# 09_-_CPU_-_SD_AUDIO_I2C_CAN.net
KiCad netlist of a schematic drawn in Altium Designer
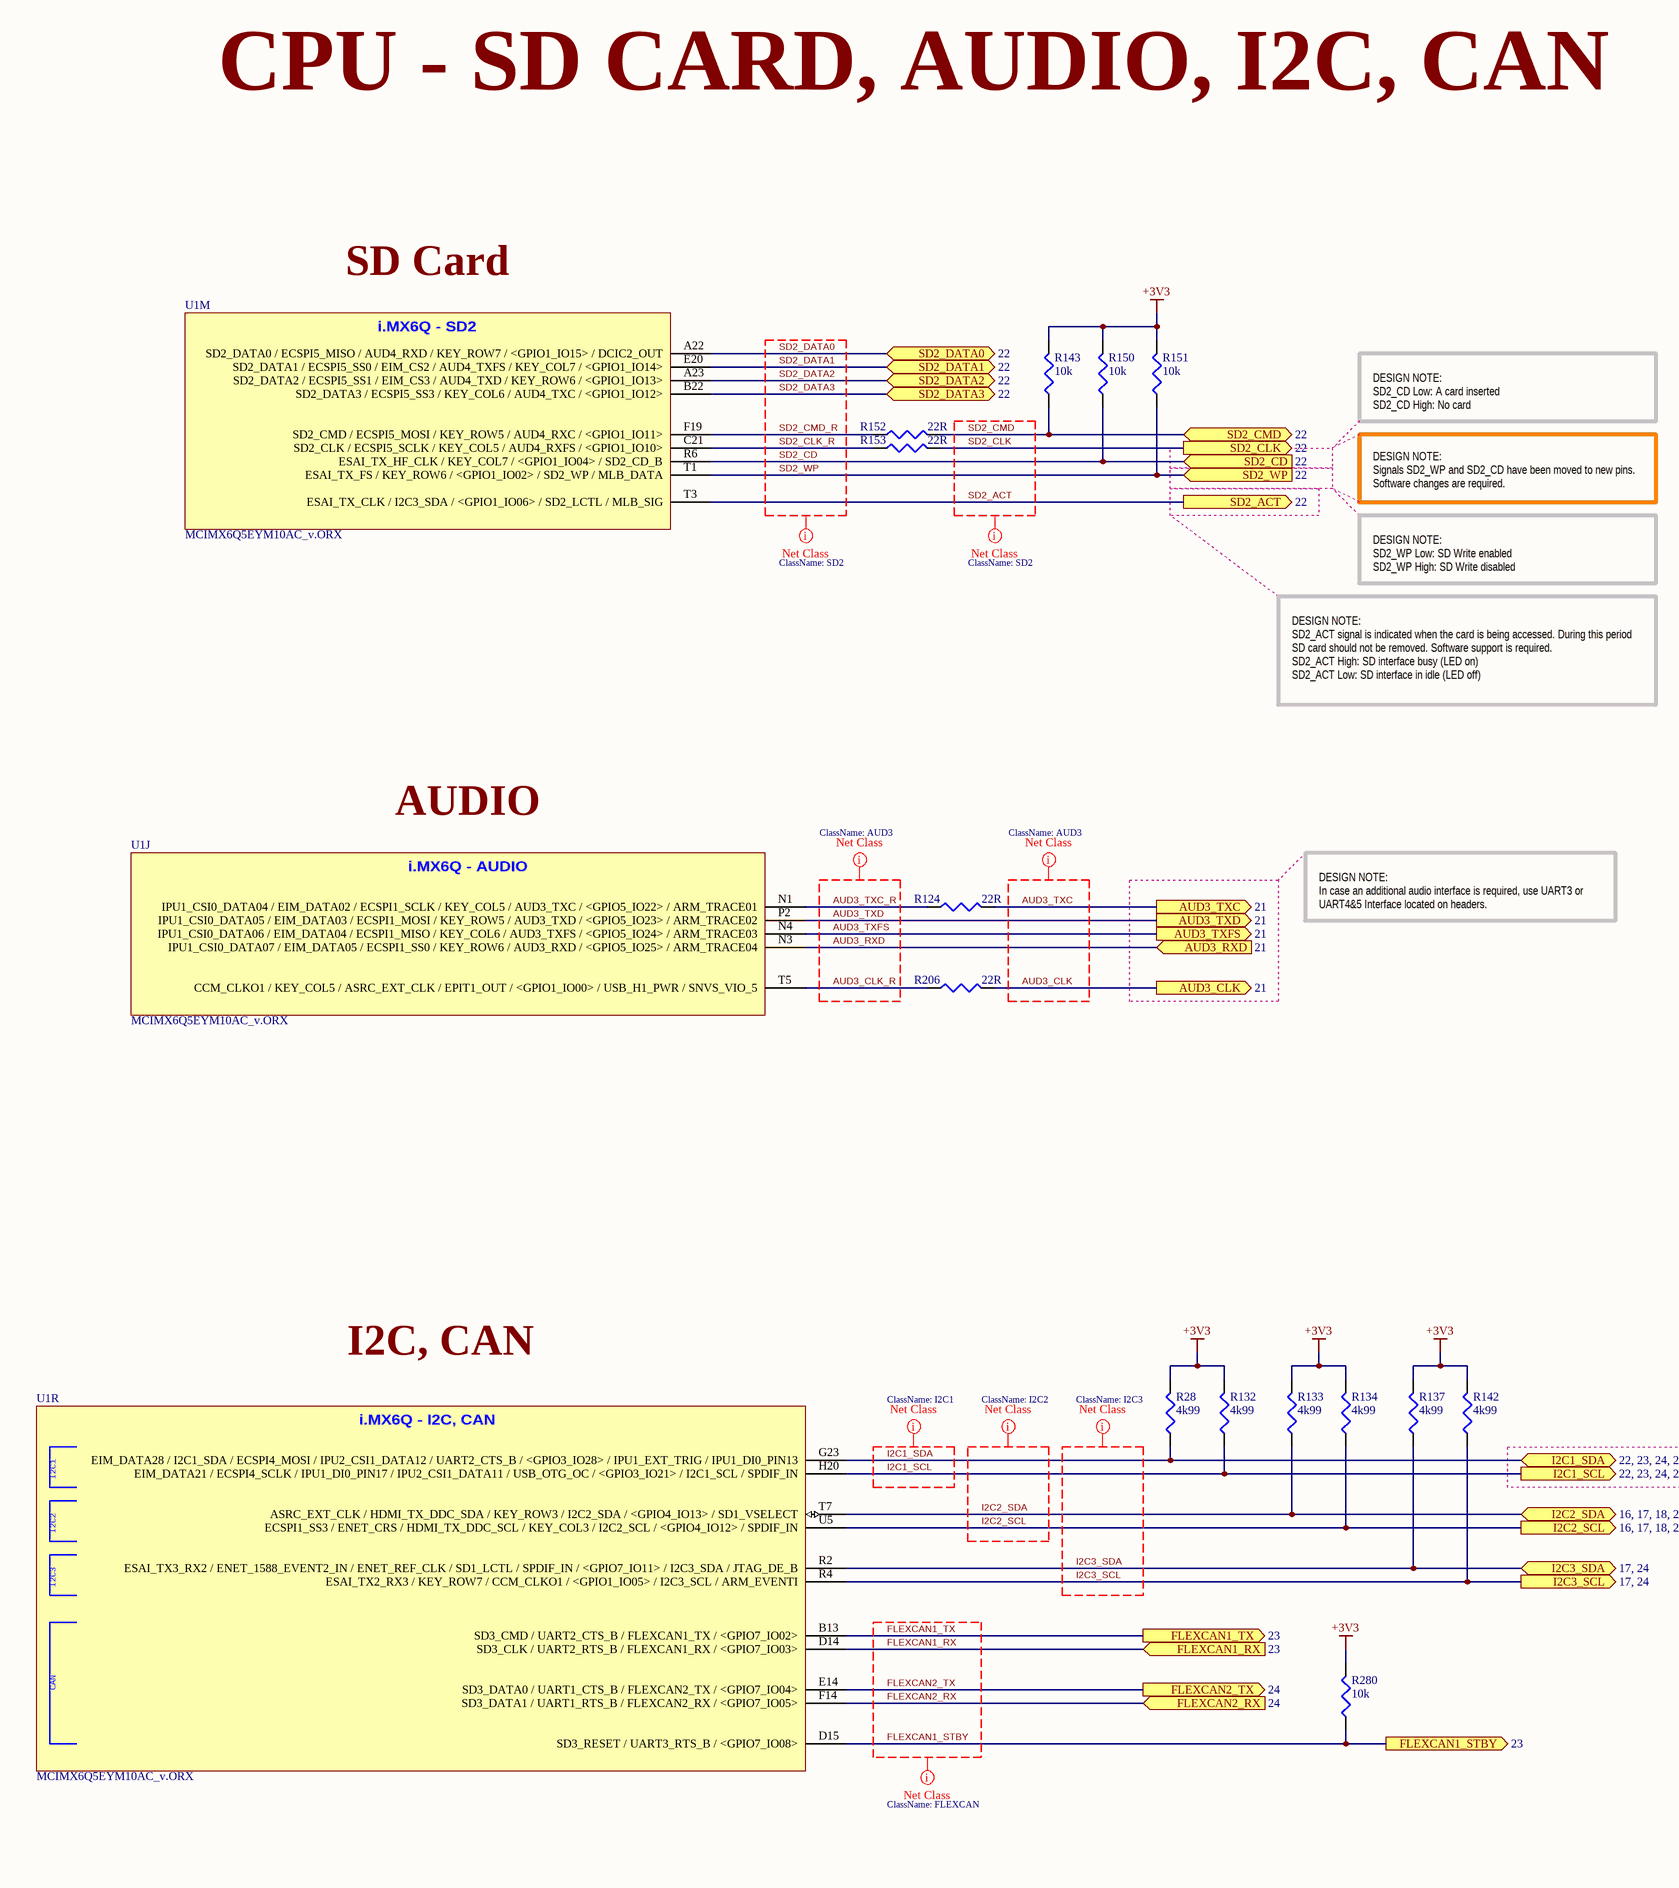
[diagram p0: [09] - CPU - SD, AUDIO, I2C, CAN.SchDoc, left]
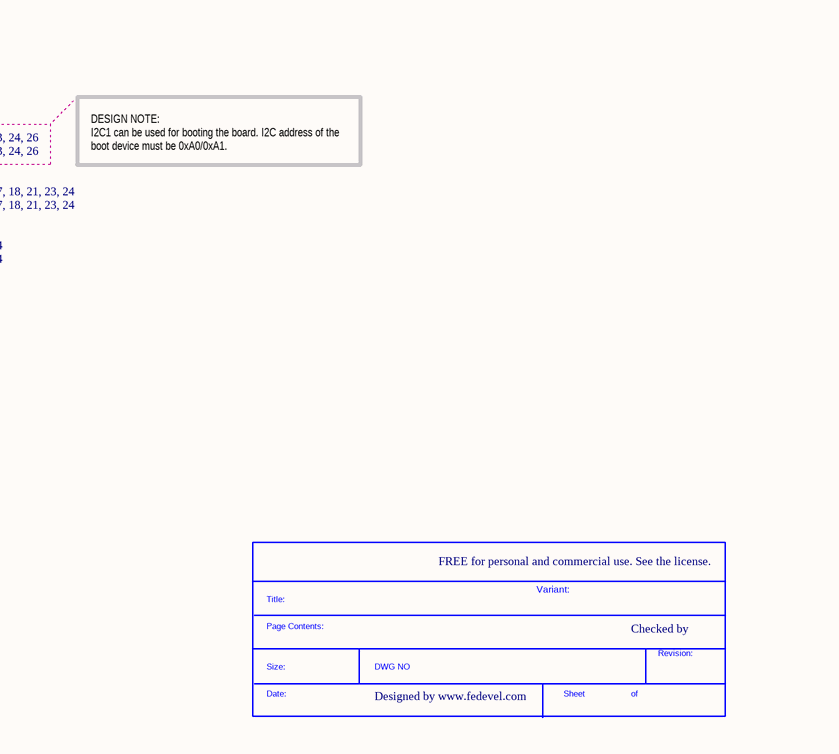
[diagram p1: [09] - CPU - SD, AUDIO, I2C, CAN.SchDoc, right]

(export (version "E")
  (design (tool "Eeschema 10.0.6"))
  (components
    (comp (ref "R28")
      (value "4k99")
      (footprint "R0402")
      (description "RES TF 4.99K OHM 1% 1/16W 0402")
      (fields
        (field (name "MANUFACTURER") "Stackpole Electronics Inc")
        (field (name "MANUFACTURER PART NUMBER") "RMCF0402FT4K99")
      )
      (libsource (lib "Integrated_Library_FEDEVEL_APR_2015") (part "RMCF0402FT4K99"))
    )
    (comp (ref "R124")
      (value "22R")
      (footprint "R0402")
      (description "RES 22.0 OHM 1/16W 1% 0402 SMD")
      (fields
        (field (name "MANUFACTURER") "Yageo")
        (field (name "MANUFACTURER PART NUMBER") "RC0402FR-0722RL")
      )
      (libsource (lib "Integrated_Library_FEDEVEL_APR_2015") (part "RC0402FR-0722RL"))
    )
    (comp (ref "R132")
      (value "4k99")
      (footprint "R0402")
      (description "RES TF 4.99K OHM 1% 1/16W 0402")
      (fields
        (field (name "MANUFACTURER") "Stackpole Electronics Inc")
        (field (name "MANUFACTURER PART NUMBER") "RMCF0402FT4K99")
      )
      (libsource (lib "Integrated_Library_FEDEVEL_APR_2015") (part "RMCF0402FT4K99"))
    )
    (comp (ref "R133")
      (value "4k99")
      (footprint "R0402")
      (description "RES TF 4.99K OHM 1% 1/16W 0402")
      (fields
        (field (name "MANUFACTURER") "Stackpole Electronics Inc")
        (field (name "MANUFACTURER PART NUMBER") "RMCF0402FT4K99")
      )
      (libsource (lib "Integrated_Library_FEDEVEL_APR_2015") (part "RMCF0402FT4K99"))
    )
    (comp (ref "R134")
      (value "4k99")
      (footprint "R0402")
      (description "RES TF 4.99K OHM 1% 1/16W 0402")
      (fields
        (field (name "MANUFACTURER") "Stackpole Electronics Inc")
        (field (name "MANUFACTURER PART NUMBER") "RMCF0402FT4K99")
      )
      (libsource (lib "Integrated_Library_FEDEVEL_APR_2015") (part "RMCF0402FT4K99"))
    )
    (comp (ref "R137")
      (value "4k99")
      (footprint "R0402")
      (description "RES TF 4.99K OHM 1% 1/16W 0402")
      (fields
        (field (name "MANUFACTURER") "Stackpole Electronics Inc")
        (field (name "MANUFACTURER PART NUMBER") "RMCF0402FT4K99")
      )
      (libsource (lib "Integrated_Library_FEDEVEL_APR_2015") (part "RMCF0402FT4K99"))
    )
    (comp (ref "R142")
      (value "4k99")
      (footprint "R0402")
      (description "RES TF 4.99K OHM 1% 1/16W 0402")
      (fields
        (field (name "MANUFACTURER") "Stackpole Electronics Inc")
        (field (name "MANUFACTURER PART NUMBER") "RMCF0402FT4K99")
      )
      (libsource (lib "Integrated_Library_FEDEVEL_APR_2015") (part "RMCF0402FT4K99"))
    )
    (comp (ref "R143")
      (value "10k")
      (footprint "R0402")
      (description "RES 10.0K OHM 1/16W 1% 0402 SMD")
      (fields
        (field (name "MANUFACTURER") "Yageo")
        (field (name "MANUFACTURER PART NUMBER") "RC0402FR-0710KL")
      )
      (libsource (lib "Integrated_Library_FEDEVEL_APR_2015") (part "RC0402FR-0710KL"))
    )
    (comp (ref "R150")
      (value "10k")
      (footprint "R0402")
      (description "RES 10.0K OHM 1/16W 1% 0402 SMD")
      (fields
        (field (name "MANUFACTURER") "Yageo")
        (field (name "MANUFACTURER PART NUMBER") "RC0402FR-0710KL")
      )
      (libsource (lib "Integrated_Library_FEDEVEL_APR_2015") (part "RC0402FR-0710KL"))
    )
    (comp (ref "R151")
      (value "10k")
      (footprint "R0402")
      (description "RES 10.0K OHM 1/16W 1% 0402 SMD")
      (fields
        (field (name "MANUFACTURER") "Yageo")
        (field (name "MANUFACTURER PART NUMBER") "RC0402FR-0710KL")
      )
      (libsource (lib "Integrated_Library_FEDEVEL_APR_2015") (part "RC0402FR-0710KL"))
    )
    (comp (ref "R152")
      (value "22R")
      (footprint "R0402")
      (description "RES 22.0 OHM 1/16W 1% 0402 SMD")
      (fields
        (field (name "MANUFACTURER") "Yageo")
        (field (name "MANUFACTURER PART NUMBER") "RC0402FR-0722RL")
      )
      (libsource (lib "Integrated_Library_FEDEVEL_APR_2015") (part "RC0402FR-0722RL"))
    )
    (comp (ref "R153")
      (value "22R")
      (footprint "R0402")
      (description "RES 22.0 OHM 1/16W 1% 0402 SMD")
      (fields
        (field (name "MANUFACTURER") "Yageo")
        (field (name "MANUFACTURER PART NUMBER") "RC0402FR-0722RL")
      )
      (libsource (lib "Integrated_Library_FEDEVEL_APR_2015") (part "RC0402FR-0722RL"))
    )
    (comp (ref "R206")
      (value "22R")
      (footprint "R0402")
      (description "RES 22.0 OHM 1/16W 1% 0402 SMD")
      (fields
        (field (name "MANUFACTURER") "Yageo")
        (field (name "MANUFACTURER PART NUMBER") "RC0402FR-0722RL")
      )
      (libsource (lib "Integrated_Library_FEDEVEL_APR_2015") (part "RC0402FR-0722RL"))
    )
    (comp (ref "R280")
      (value "10k")
      (footprint "R0402")
      (description "RES 10.0K OHM 1/16W 1% 0402 SMD")
      (fields
        (field (name "MANUFACTURER") "Yageo")
        (field (name "MANUFACTURER PART NUMBER") "RC0402FR-0710KL")
      )
      (libsource (lib "Integrated_Library_FEDEVEL_APR_2015") (part "RC0402FR-0710KL"))
    )
    (comp (ref "U1")
      (value "MCIMX6Q5EYM10AC_v.ORX")
      (footprint "PBGA624")
      (description "IC MCU 32BIT ARM QUAD 624FCBGA")
      (fields
        (field (name "MANUFACTURER") "Freescale Semiconductor")
        (field (name "MANUFACTURER PART NUMBER") "MCIMX6Q5EYM10AC")
        (field (name ".CREATOR") "MM")
        (field (name ".CHECKED PCB") "MM, checked by RF")
      )
      (libsource (lib "Integrated_Library_FEDEVEL_APR_2015") (part "MCIMX6Q5EYM10AC_v.ORX"))
    )
  )
  (nets
    (net (code "1") (name "+3V3") (class "Default")
      (node (ref "R132") (pin "2") (pinfunction "2_2") (pintype "passive"))
      (node (ref "R133") (pin "2") (pinfunction "2_2") (pintype "passive"))
      (node (ref "R134") (pin "2") (pinfunction "2_2") (pintype "passive"))
      (node (ref "R137") (pin "2") (pinfunction "2_2") (pintype "passive"))
      (node (ref "R142") (pin "2") (pinfunction "2_2") (pintype "passive"))
      (node (ref "R143") (pin "2") (pinfunction "2_2") (pintype "passive"))
      (node (ref "R150") (pin "2") (pinfunction "2_2") (pintype "passive"))
      (node (ref "R151") (pin "2") (pinfunction "2_2") (pintype "passive"))
      (node (ref "R28") (pin "2") (pinfunction "2_2") (pintype "passive"))
      (node (ref "R280") (pin "2") (pinfunction "2_2") (pintype "passive"))
    )
    (net (code "2") (name "/AUD3_CLK") (class "Default")
      (node (ref "R206") (pin "2") (pinfunction "2_2") (pintype "passive"))
    )
    (net (code "3") (name "/AUD3_CLK_R") (class "Default")
      (node (ref "R206") (pin "1") (pinfunction "1_1") (pintype "passive"))
      (node (ref "U1") (pin "T5") (pinfunction "CCM_CLKO1_/_KEY_COL5_/_ASRC_EXT_CLK_/_EPIT1_OUT_/_<GPIO1_IO00>_/_USB_H1_PWR_/_SNVS_VIO_5_T5") (pintype "passive"))
    )
    (net (code "4") (name "/AUD3_RXD") (class "Default")
      (node (ref "U1") (pin "N3") (pinfunction "IPU1_CSI0_DATA07_/_EIM_DATA05_/_ECSPI1_SS0_/_KEY_ROW6_/_AUD3_RXD_/_<GPIO5_IO25>_/_ARM_TRACE04_N3") (pintype "passive"))
    )
    (net (code "5") (name "/AUD3_TXC") (class "Default")
      (node (ref "R124") (pin "2") (pinfunction "2_2") (pintype "passive"))
    )
    (net (code "6") (name "/AUD3_TXC_R") (class "Default")
      (node (ref "R124") (pin "1") (pinfunction "1_1") (pintype "passive"))
      (node (ref "U1") (pin "N1") (pinfunction "IPU1_CSI0_DATA04_/_EIM_DATA02_/_ECSPI1_SCLK_/_KEY_COL5_/_AUD3_TXC_/_<GPIO5_IO22>_/_ARM_TRACE01_N1") (pintype "passive"))
    )
    (net (code "7") (name "/AUD3_TXD") (class "Default")
      (node (ref "U1") (pin "P2") (pinfunction "IPU1_CSI0_DATA05_/_EIM_DATA03_/_ECSPI1_MOSI_/_KEY_ROW5_/_AUD3_TXD_/_<GPIO5_IO23>_/_ARM_TRACE02_P2") (pintype "passive"))
    )
    (net (code "8") (name "/AUD3_TXFS") (class "Default")
      (node (ref "U1") (pin "N4") (pinfunction "IPU1_CSI0_DATA06_/_EIM_DATA04_/_ECSPI1_MISO_/_KEY_COL6_/_AUD3_TXFS_/_<GPIO5_IO24>_/_ARM_TRACE03_N4") (pintype "passive"))
    )
    (net (code "9") (name "/FLEXCAN1_RX") (class "Default")
      (node (ref "U1") (pin "D14") (pinfunction "SD3_CLK_/_UART2_RTS_B_/_FLEXCAN1_RX_/_<GPIO7_IO03>_D14") (pintype "passive"))
    )
    (net (code "10") (name "/FLEXCAN1_STBY") (class "Default")
      (node (ref "R280") (pin "1") (pinfunction "1_1") (pintype "passive"))
      (node (ref "U1") (pin "D15") (pinfunction "SD3_RESET_/_UART3_RTS_B_/_<GPIO7_IO08>_D15") (pintype "passive"))
    )
    (net (code "11") (name "/FLEXCAN1_TX") (class "Default")
      (node (ref "U1") (pin "B13") (pinfunction "SD3_CMD_/_UART2_CTS_B_/_FLEXCAN1_TX_/_<GPIO7_IO02>_B13") (pintype "passive"))
    )
    (net (code "12") (name "/FLEXCAN2_RX") (class "Default")
      (node (ref "U1") (pin "F14") (pinfunction "SD3_DATA1_/_UART1_RTS_B_/_FLEXCAN2_RX_/_<GPIO7_IO05>_F14") (pintype "passive"))
    )
    (net (code "13") (name "/FLEXCAN2_TX") (class "Default")
      (node (ref "U1") (pin "E14") (pinfunction "SD3_DATA0_/_UART1_CTS_B_/_FLEXCAN2_TX_/_<GPIO7_IO04>_E14") (pintype "passive"))
    )
    (net (code "14") (name "/I2C1_SCL") (class "Default")
      (node (ref "R132") (pin "1") (pinfunction "1_1") (pintype "passive"))
      (node (ref "U1") (pin "H20") (pinfunction "EIM_DATA21_/_ECSPI4_SCLK_/_IPU1_DI0_PIN17_/_IPU2_CSI1_DATA11_/_USB_OTG_OC_/_<GPIO3_IO21>_/_I2C1_SCL_/_SPDIF_IN_H20") (pintype "passive"))
    )
    (net (code "15") (name "/I2C1_SDA") (class "Default")
      (node (ref "R28") (pin "1") (pinfunction "1_1") (pintype "passive"))
      (node (ref "U1") (pin "G23") (pinfunction "EIM_DATA28_/_I2C1_SDA_/_ECSPI4_MOSI_/_IPU2_CSI1_DATA12_/_UART2_CTS_B_/_<GPIO3_IO28>_/_IPU1_EXT_TRIG_/_IPU1_DI0_PIN13_G23") (pintype "passive"))
    )
    (net (code "16") (name "/I2C2_SCL") (class "Default")
      (node (ref "R134") (pin "1") (pinfunction "1_1") (pintype "passive"))
      (node (ref "U1") (pin "U5") (pinfunction "ECSPI1_SS3_/_ENET_CRS_/_HDMI_TX_DDC_SCL_/_KEY_COL3_/_I2C2_SCL_/_<GPIO4_IO12>_/_SPDIF_IN_U5") (pintype "passive"))
    )
    (net (code "17") (name "/I2C2_SDA") (class "Default")
      (node (ref "R133") (pin "1") (pinfunction "1_1") (pintype "passive"))
      (node (ref "U1") (pin "T7") (pinfunction "ASRC_EXT_CLK_/_HDMI_TX_DDC_SDA_/_KEY_ROW3_/_I2C2_SDA_/_<GPIO4_IO13>_/_SD1_VSELECT_T7") (pintype "bidirectional"))
    )
    (net (code "18") (name "/I2C3_SCL") (class "Default")
      (node (ref "R142") (pin "1") (pinfunction "1_1") (pintype "passive"))
      (node (ref "U1") (pin "R4") (pinfunction "ESAI_TX2_RX3_/_KEY_ROW7_/_CCM_CLKO1_/_<GPIO1_IO05>_/_I2C3_SCL_/_ARM_EVENTI_R4") (pintype "passive"))
    )
    (net (code "19") (name "/I2C3_SDA") (class "Default")
      (node (ref "R137") (pin "1") (pinfunction "1_1") (pintype "passive"))
      (node (ref "U1") (pin "R2") (pinfunction "ESAI_TX3_RX2_/_ENET_1588_EVENT2_IN_/_ENET_REF_CLK_/_SD1_LCTL_/_SPDIF_IN_/_<GPIO7_IO11>_/_I2C3_SDA_/_JTAG_DE_B_R2") (pintype "passive"))
    )
    (net (code "20") (name "/SD2_ACT") (class "Default")
      (node (ref "U1") (pin "T3") (pinfunction "ESAI_TX_CLK_/_I2C3_SDA_/_<GPIO1_IO06>_/_SD2_LCTL_/_MLB_SIG_T3") (pintype "passive"))
    )
    (net (code "21") (name "/SD2_CD") (class "Default")
      (node (ref "R150") (pin "1") (pinfunction "1_1") (pintype "passive"))
      (node (ref "U1") (pin "R6") (pinfunction "ESAI_TX_HF_CLK_/_KEY_COL7_/_<GPIO1_IO04>_/_SD2_CD_B_R6") (pintype "passive"))
    )
    (net (code "22") (name "/SD2_CLK") (class "Default")
      (node (ref "R153") (pin "2") (pinfunction "2_2") (pintype "passive"))
    )
    (net (code "23") (name "/SD2_CLK_R") (class "Default")
      (node (ref "R153") (pin "1") (pinfunction "1_1") (pintype "passive"))
      (node (ref "U1") (pin "C21") (pinfunction "SD2_CLK_/_ECSPI5_SCLK_/_KEY_COL5_/_AUD4_RXFS_/_<GPIO1_IO10>_C21") (pintype "passive"))
    )
    (net (code "24") (name "/SD2_CMD") (class "Default")
      (node (ref "R143") (pin "1") (pinfunction "1_1") (pintype "passive"))
      (node (ref "R152") (pin "2") (pinfunction "2_2") (pintype "passive"))
    )
    (net (code "25") (name "/SD2_CMD_R") (class "Default")
      (node (ref "R152") (pin "1") (pinfunction "1_1") (pintype "passive"))
      (node (ref "U1") (pin "F19") (pinfunction "SD2_CMD_/_ECSPI5_MOSI_/_KEY_ROW5_/_AUD4_RXC_/_<GPIO1_IO11>_F19") (pintype "passive"))
    )
    (net (code "26") (name "/SD2_DATA0") (class "Default")
      (node (ref "U1") (pin "A22") (pinfunction "SD2_DATA0_/_ECSPI5_MISO_/_AUD4_RXD_/_KEY_ROW7_/_<GPIO1_IO15>_/_DCIC2_OUT_A22") (pintype "passive"))
    )
    (net (code "27") (name "/SD2_DATA1") (class "Default")
      (node (ref "U1") (pin "E20") (pinfunction "SD2_DATA1_/_ECSPI5_SS0_/_EIM_CS2_/_AUD4_TXFS_/_KEY_COL7_/_<GPIO1_IO14>_E20") (pintype "passive"))
    )
    (net (code "28") (name "/SD2_DATA2") (class "Default")
      (node (ref "U1") (pin "A23") (pinfunction "SD2_DATA2_/_ECSPI5_SS1_/_EIM_CS3_/_AUD4_TXD_/_KEY_ROW6_/_<GPIO1_IO13>_A23") (pintype "passive"))
    )
    (net (code "29") (name "/SD2_DATA3") (class "Default")
      (node (ref "U1") (pin "B22") (pinfunction "SD2_DATA3_/_ECSPI5_SS3_/_KEY_COL6_/_AUD4_TXC_/_<GPIO1_IO12>_B22") (pintype "passive"))
    )
    (net (code "30") (name "/SD2_WP") (class "Default")
      (node (ref "R151") (pin "1") (pinfunction "1_1") (pintype "passive"))
      (node (ref "U1") (pin "T1") (pinfunction "ESAI_TX_FS_/_KEY_ROW6_/_<GPIO1_IO02>_/_SD2_WP_/_MLB_DATA_T1") (pintype "passive"))
    )
  )
)
